# PMIC.net
KiCad netlist of a schematic drawn in Altium Designer
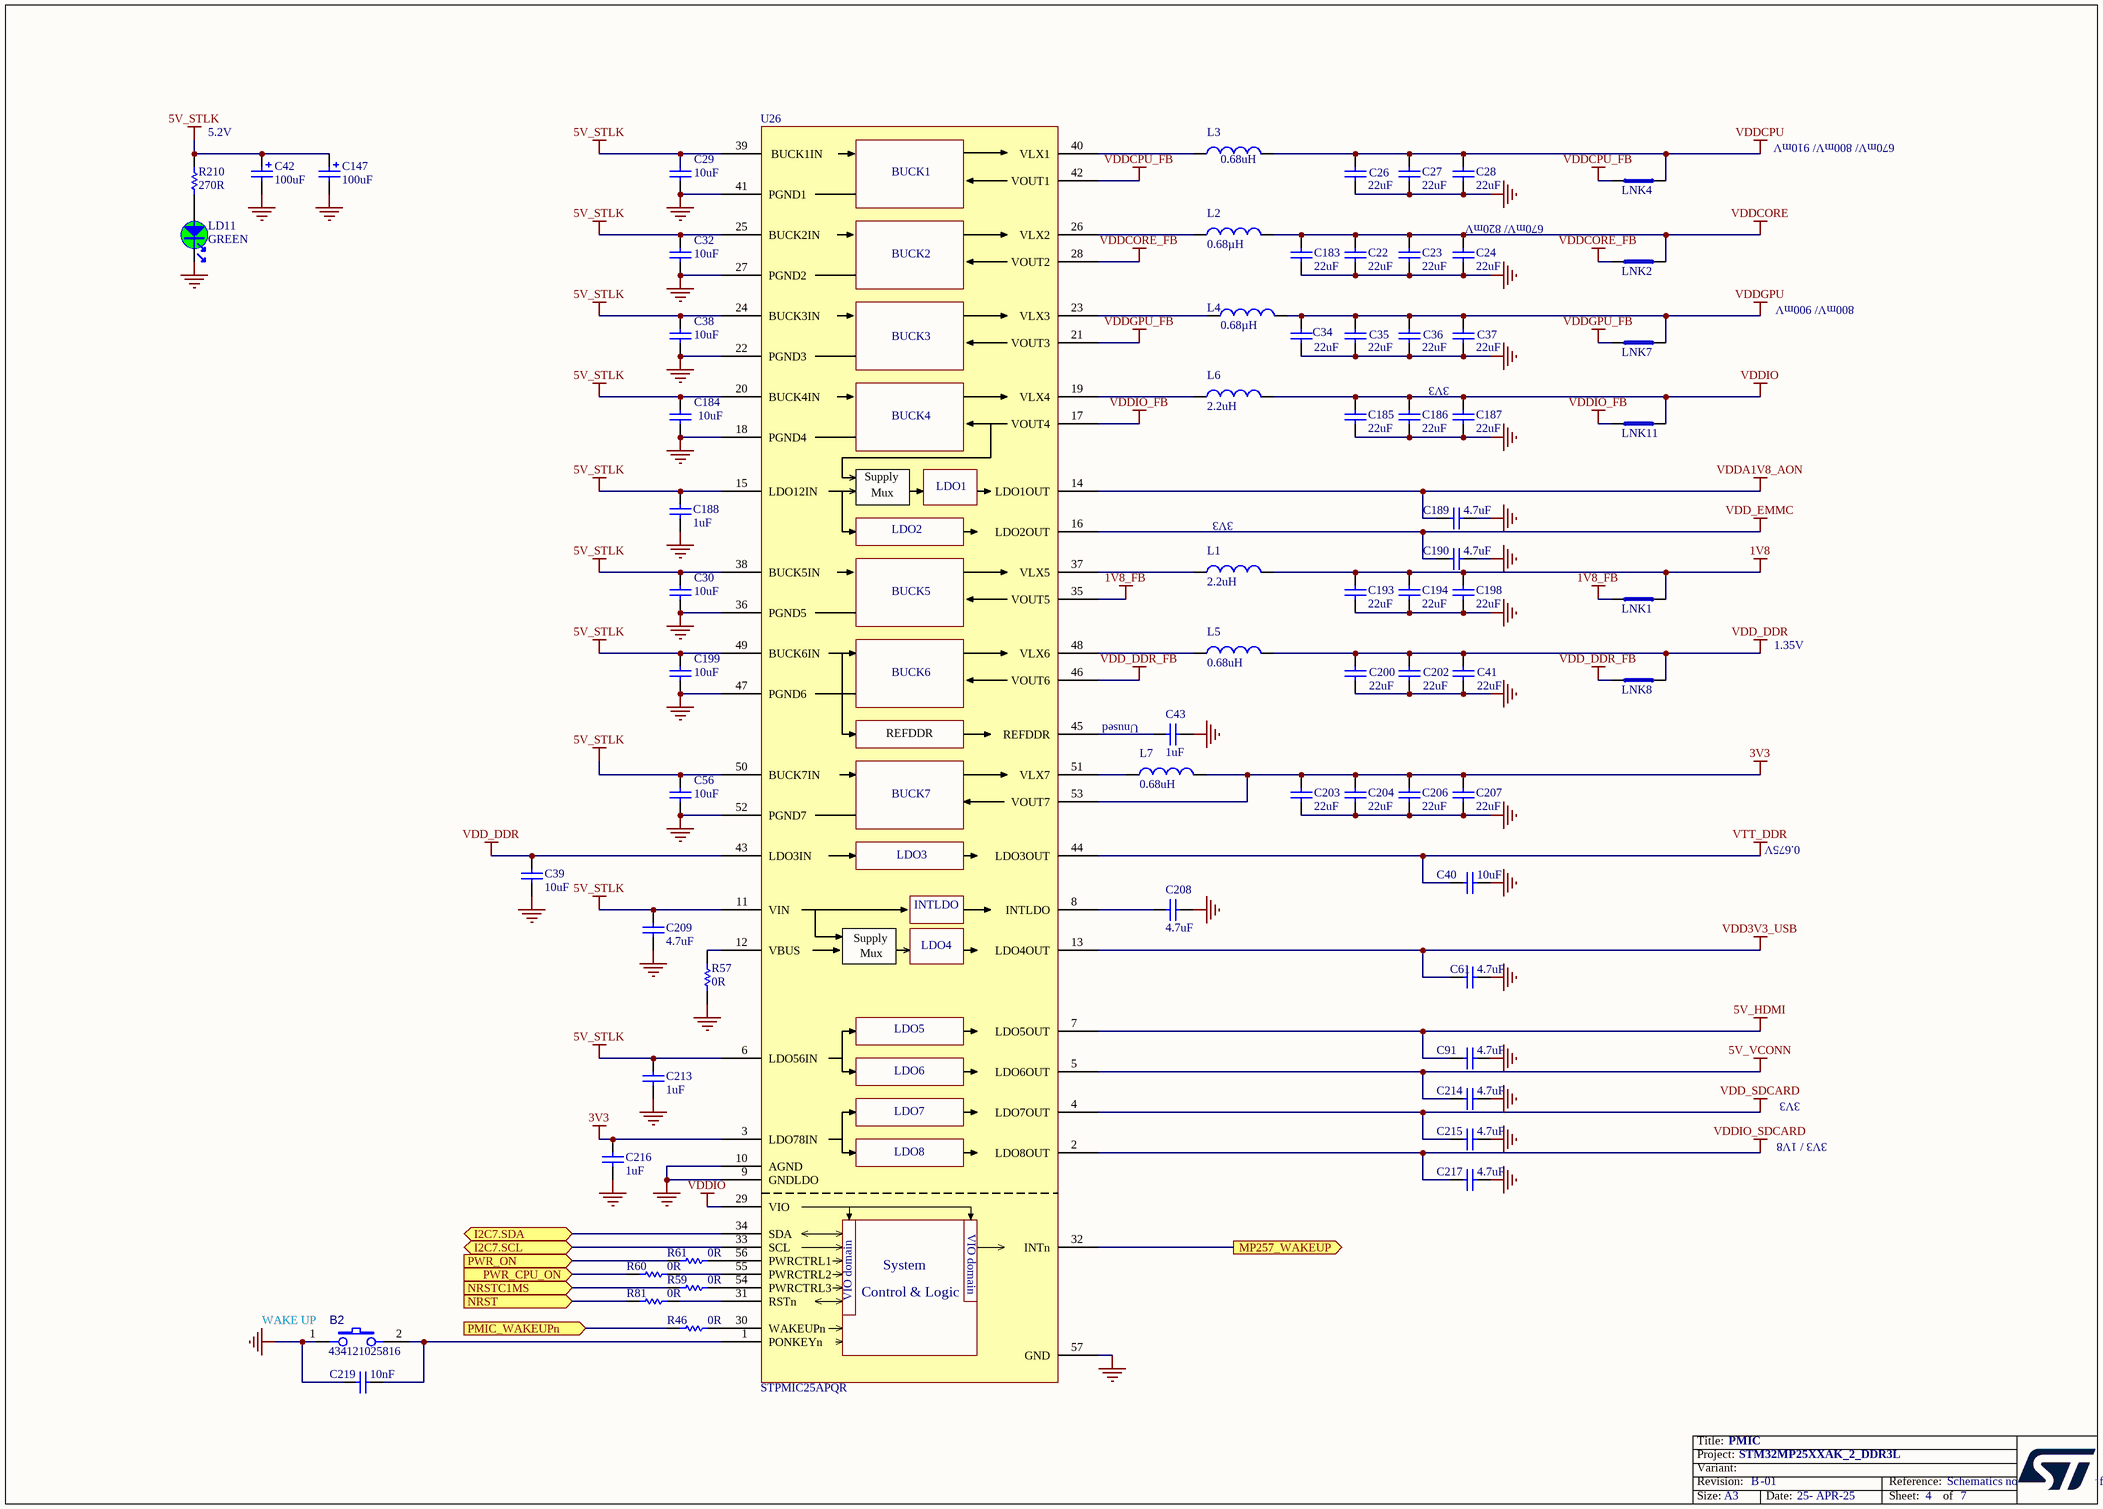
[diagram p0: PMIC.SchDoc]

(export (version "E")
  (design (tool "Eeschema 10.0.6"))
  (components
    (comp (ref "B2")
      (value "434121025816")
      (footprint "SWI_WE_434121025816")
      (description "Switch tactile, SPST-NO, 50mA, 12V, 6x3.8mm")
      (fields
        (field (name "INTERNAL_PART_NUMBER") "MCD-03492")
        (field (name "MANUFACTURER") "WURTH ELEKTRONIC")
      )
      (libsource (lib "MCD_PARTS_database") (part "SW_PUSH_SMD_2P"))
    )
    (comp (ref "C22")
      (value "22uF")
      (footprint "C0603")
      (description "Capacitor, MLCC, 22uF, 6V3, X5R, +/-20%, 0603, T=0,8mm")
      (fields
        (field (name "INTERNAL_PART_NUMBER") "MCD-00100")
        (field (name "MANUFACTURER_PART_NUMBER") "GRM188R60J226MEA0J")
      )
      (libsource (lib "MCD_PARTS_database") (part "Capacitor"))
    )
    (comp (ref "C23")
      (value "22uF")
      (footprint "C0603")
      (description "Capacitor, MLCC, 22uF, 6V3, X5R, +/-20%, 0603, T=0,8mm")
      (fields
        (field (name "INTERNAL_PART_NUMBER") "MCD-00100")
        (field (name "MANUFACTURER_PART_NUMBER") "GRM188R60J226MEA0J")
      )
      (libsource (lib "MCD_PARTS_database") (part "Capacitor"))
    )
    (comp (ref "C24")
      (value "22uF")
      (footprint "C0603")
      (description "Capacitor, MLCC, 22uF, 6V3, X5R, +/-20%, 0603, T=0,8mm")
      (fields
        (field (name "INTERNAL_PART_NUMBER") "MCD-00100")
        (field (name "MANUFACTURER_PART_NUMBER") "GRM188R60J226MEA0J")
      )
      (libsource (lib "MCD_PARTS_database") (part "Capacitor"))
    )
    (comp (ref "C26")
      (value "22uF")
      (footprint "C0603")
      (description "Capacitor, MLCC, 22uF, 6V3, X5R, +/-20%, 0603, T=0,8mm")
      (fields
        (field (name "INTERNAL_PART_NUMBER") "MCD-00100")
        (field (name "MANUFACTURER_PART_NUMBER") "GRM188R60J226MEA0J")
      )
      (libsource (lib "MCD_PARTS_database") (part "Capacitor"))
    )
    (comp (ref "C27")
      (value "22uF")
      (footprint "C0603")
      (description "Capacitor, MLCC, 22uF, 6V3, X5R, +/-20%, 0603, T=0,8mm")
      (fields (field (name "INTERNAL_PART_NUMBER") "MCD-00100") (field (name "MANUFACTURER") "MURATA"))
      (libsource (lib "MCD_PARTS_database") (part "Capacitor"))
    )
    (comp (ref "C28")
      (value "22uF")
      (footprint "C0603")
      (description "Capacitor, MLCC, 22uF, 6V3, X5R, +/-20%, 0603, T=0,8mm")
      (fields (field (name "INTERNAL_PART_NUMBER") "MCD-00100") (field (name "MANUFACTURER") "MURATA"))
      (libsource (lib "MCD_PARTS_database") (part "Capacitor"))
    )
    (comp (ref "C29")
      (value "10uF")
      (footprint "C0603")
      (description "Capacitor, MLCC, 10uF, 10V, X5R, +/-10%, 0603, T=0,8mm")
      (fields
        (field (name "INTERNAL_PART_NUMBER") "MCD-00099")
        (field (name "MANUFACTURER_PART_NUMBER") "GRM188R61A106KE69D")
      )
      (libsource (lib "MCD_PARTS_database") (part "Capacitor"))
    )
    (comp (ref "C30")
      (value "10uF")
      (footprint "C0603")
      (description "Capacitor, MLCC, 10uF, 10V, X5R, +/-10%, 0603, T=0,8mm")
      (fields
        (field (name "INTERNAL_PART_NUMBER") "MCD-00099")
        (field (name "MANUFACTURER_PART_NUMBER") "GRM188R61A106KE69D")
      )
      (libsource (lib "MCD_PARTS_database") (part "Capacitor"))
    )
    (comp (ref "C32")
      (value "10uF")
      (footprint "C0603")
      (description "Capacitor, MLCC, 10uF, 10V, X5R, +/-10%, 0603, T=0,8mm")
      (fields
        (field (name "INTERNAL_PART_NUMBER") "MCD-00099")
        (field (name "MANUFACTURER_PART_NUMBER") "GRM188R61A106KE69D")
      )
      (libsource (lib "MCD_PARTS_database") (part "Capacitor"))
    )
    (comp (ref "C34")
      (value "22uF")
      (footprint "C0603")
      (description "Capacitor, MLCC, 22uF, 6V3, X5R, +/-20%, 0603, T=0,8mm")
      (fields
        (field (name "INTERNAL_PART_NUMBER") "MCD-00100")
        (field (name "MANUFACTURER_PART_NUMBER") "GRM188R60J226MEA0J")
      )
      (libsource (lib "MCD_PARTS_database") (part "Capacitor"))
    )
    (comp (ref "C35")
      (value "22uF")
      (footprint "C0603")
      (description "Capacitor, MLCC, 22uF, 6V3, X5R, +/-20%, 0603, T=0,8mm")
      (fields
        (field (name "INTERNAL_PART_NUMBER") "MCD-00100")
        (field (name "MANUFACTURER_PART_NUMBER") "GRM188R60J226MEA0J")
      )
      (libsource (lib "MCD_PARTS_database") (part "Capacitor"))
    )
    (comp (ref "C36")
      (value "22uF")
      (footprint "C0603")
      (description "Capacitor, MLCC, 22uF, 6V3, X5R, +/-20%, 0603, T=0,8mm")
      (fields
        (field (name "INTERNAL_PART_NUMBER") "MCD-00100")
        (field (name "MANUFACTURER_PART_NUMBER") "GRM188R60J226MEA0J")
      )
      (libsource (lib "MCD_PARTS_database") (part "Capacitor"))
    )
    (comp (ref "C37")
      (value "22uF")
      (footprint "C0603")
      (description "Capacitor, MLCC, 22uF, 6V3, X5R, +/-20%, 0603, T=0,8mm")
      (fields
        (field (name "INTERNAL_PART_NUMBER") "MCD-00100")
        (field (name "MANUFACTURER_PART_NUMBER") "GRM188R60J226MEA0J")
      )
      (libsource (lib "MCD_PARTS_database") (part "Capacitor"))
    )
    (comp (ref "C38")
      (value "10uF")
      (footprint "C0603")
      (description "Capacitor, MLCC, 10uF, 10V, X5R, +/-10%, 0603, T=0,8mm")
      (fields
        (field (name "INTERNAL_PART_NUMBER") "MCD-00099")
        (field (name "MANUFACTURER_PART_NUMBER") "GRM188R61A106KE69D")
      )
      (libsource (lib "MCD_PARTS_database") (part "Capacitor"))
    )
    (comp (ref "C39")
      (value "10uF")
      (footprint "MCD_PARTS:C0402")
      (description "Capacitor, MLCC, 10uF, 6.3V, X5R, +/-20%, 0402, T=0.5mm")
      (fields (field (name "INTERNAL_PART_NUMBER") "MCD-03140") (field (name "MANUFACTURER") "MURATA"))
      (libsource (lib "MCD_PARTS_database") (part "Capacitor"))
    )
    (comp (ref "C40")
      (value "10uF")
      (footprint "C0402")
      (description "Capacitor, MLCC, 10uF, 6.3V, X5R, +/-20%, 0402, T=0.5mm")
      (fields (field (name "INTERNAL_PART_NUMBER") "MCD-03140") (field (name "MANUFACTURER") "MURATA"))
      (libsource (lib "MCD_PARTS_database") (part "Capacitor"))
    )
    (comp (ref "C41")
      (value "22uF")
      (footprint "C0603")
      (description "Capacitor, MLCC, 22uF, 6V3, X5R, +/-20%, 0603, T=0,8mm")
      (fields
        (field (name "INTERNAL_PART_NUMBER") "MCD-00100")
        (field (name "MANUFACTURER_PART_NUMBER") "GRM188R60J226MEA0J")
      )
      (libsource (lib "MCD_PARTS_database") (part "Capacitor"))
    )
    (comp (ref "C42")
      (value "100uF")
      (footprint "CPOL_TCJ-B_1210_H210")
      (description "Capacitor, Tantalum, 100uF, 6V3, 40mR, +/-20%,  Type_B (3528 metric), T=1.9mm")
      (fields (field (name "INTERNAL_PART_NUMBER") "MCD-01796") (field (name "MANUFACTURER") "AVX"))
      (libsource (lib "MCD_PARTS_database") (part "Cap_POL_TANA"))
    )
    (comp (ref "C43")
      (value "1uF")
      (footprint "C0402")
      (description "Capacitor, MLCC, 1uF, 25V, X5R, +/-10%, 0402, T=0.5mm")
      (fields (field (name "INTERNAL_PART_NUMBER") "MCD-00095") (field (name "MANUFACTURER") "MURATA"))
      (libsource (lib "MCD_PARTS_database") (part "Capacitor"))
    )
    (comp (ref "C56")
      (value "10uF")
      (footprint "C0603")
      (description "Capacitor, MLCC, 10uF, 10V, X5R, +/-10%, 0603, T=0,8mm")
      (fields
        (field (name "INTERNAL_PART_NUMBER") "MCD-00099")
        (field (name "MANUFACTURER_PART_NUMBER") "GRM188R61A106KE69D")
      )
      (libsource (lib "MCD_PARTS_database") (part "Capacitor"))
    )
    (comp (ref "C61")
      (value "4.7uF")
      (footprint "C0402")
      (description "Capacitor, MLCC, 4.7uF, 6V3, X5R, +/-20%, 0402, T=0.5mm")
      (fields
        (field (name "INTERNAL_PART_NUMBER") "MCD-01356")
        (field (name "MANUFACTURER_PART_NUMBER") "GRM155R60J475ME47")
      )
      (libsource (lib "MCD_PARTS_database") (part "Capacitor"))
    )
    (comp (ref "C91")
      (value "4.7uF")
      (footprint "C0402")
      (description "Capacitor, MLCC, 4.7uF, 6V3, X5R, +/-20%, 0402, T=0.5mm")
      (fields
        (field (name "INTERNAL_PART_NUMBER") "MCD-01356")
        (field (name "MANUFACTURER_PART_NUMBER") "GRM155R60J475ME47")
      )
      (libsource (lib "MCD_PARTS_database") (part "Capacitor"))
    )
    (comp (ref "C147")
      (value "100uF")
      (footprint "CPOL_TCJ-B_1210_H210")
      (description "Capacitor, Tantalum, 100uF, 6V3, 40mR, +/-20%,  Type_B (3528 metric), T=1.9mm")
      (fields (field (name "INTERNAL_PART_NUMBER") "MCD-01796") (field (name "MANUFACTURER") "AVX"))
      (libsource (lib "MCD_PARTS_database") (part "Cap_POL_TANA"))
    )
    (comp (ref "C183")
      (value "22uF")
      (footprint "C0603")
      (description "Capacitor, MLCC, 22uF, 6V3, X5R, +/-20%, 0603, T=0,8mm")
      (fields (field (name "INTERNAL_PART_NUMBER") "MCD-00100") (field (name "MANUFACTURER") "MURATA"))
      (libsource (lib "MCD_PARTS_database") (part "Capacitor"))
    )
    (comp (ref "C184")
      (value "10uF")
      (footprint "C0603")
      (description "Capacitor, MLCC, 10uF, 10V, X5R, +/-10%, 0603, T=0,8mm")
      (fields
        (field (name "INTERNAL_PART_NUMBER") "MCD-00099")
        (field (name "MANUFACTURER_PART_NUMBER") "GRM188R61A106KE69D")
      )
      (libsource (lib "MCD_PARTS_database") (part "Capacitor"))
    )
    (comp (ref "C185")
      (value "22uF")
      (footprint "C0805")
      (description "Capacitor, MLCC, 22uF, 10V, X5R, +/-20%, 0805, T=1,25mm")
      (fields (field (name "INTERNAL_PART_NUMBER") "MCD-03139") (field (name "MANUFACTURER") "MURATA"))
      (libsource (lib "MCD_PARTS_database") (part "Capacitor"))
    )
    (comp (ref "C186")
      (value "22uF")
      (footprint "C0805")
      (description "Capacitor, MLCC, 22uF, 10V, X5R, +/-20%, 0805, T=1,25mm")
      (fields (field (name "INTERNAL_PART_NUMBER") "MCD-03139") (field (name "MANUFACTURER") "MURATA"))
      (libsource (lib "MCD_PARTS_database") (part "Capacitor"))
    )
    (comp (ref "C187")
      (value "22uF")
      (footprint "C0805")
      (description "Capacitor, MLCC, 22uF, 10V, X5R, +/-20%, 0805, T=1,25mm")
      (fields (field (name "INTERNAL_PART_NUMBER") "MCD-03139") (field (name "MANUFACTURER") "MURATA"))
      (libsource (lib "MCD_PARTS_database") (part "Capacitor"))
    )
    (comp (ref "C188")
      (value "1uF")
      (footprint "C0402")
      (description "Capacitor, MLCC, 1uF, 25V, X5R, +/-10%, 0402, T=0.5mm")
      (fields (field (name "INTERNAL_PART_NUMBER") "MCD-00095") (field (name "MANUFACTURER") "MURATA"))
      (libsource (lib "MCD_PARTS_database") (part "Capacitor"))
    )
    (comp (ref "C189")
      (value "4.7uF")
      (footprint "C0402")
      (description "Capacitor, MLCC, 4.7uF, 6V3, X5R, +/-20%, 0402, T=0.5mm")
      (fields
        (field (name "INTERNAL_PART_NUMBER") "MCD-01356")
        (field (name "MANUFACTURER_PART_NUMBER") "GRM155R60J475ME47")
      )
      (libsource (lib "MCD_PARTS_database") (part "Capacitor"))
    )
    (comp (ref "C190")
      (value "4.7uF")
      (footprint "C0402")
      (description "Capacitor, MLCC, 4.7uF, 6V3, X5R, +/-20%, 0402, T=0.5mm")
      (fields
        (field (name "INTERNAL_PART_NUMBER") "MCD-01356")
        (field (name "MANUFACTURER_PART_NUMBER") "GRM155R60J475ME47")
      )
      (libsource (lib "MCD_PARTS_database") (part "Capacitor"))
    )
    (comp (ref "C193")
      (value "22uF")
      (footprint "C0805")
      (description "Capacitor, MLCC, 22uF, 10V, X5R, +/-20%, 0805, T=1,25mm")
      (fields (field (name "INTERNAL_PART_NUMBER") "MCD-03139") (field (name "MANUFACTURER") "MURATA"))
      (libsource (lib "MCD_PARTS_database") (part "Capacitor"))
    )
    (comp (ref "C194")
      (value "22uF")
      (footprint "C0805")
      (description "Capacitor, MLCC, 22uF, 10V, X5R, +/-20%, 0805, T=1,25mm")
      (fields (field (name "INTERNAL_PART_NUMBER") "MCD-03139") (field (name "MANUFACTURER") "MURATA"))
      (libsource (lib "MCD_PARTS_database") (part "Capacitor"))
    )
    (comp (ref "C198")
      (value "22uF")
      (footprint "C0805")
      (description "Capacitor, MLCC, 22uF, 10V, X5R, +/-20%, 0805, T=1,25mm")
      (fields (field (name "INTERNAL_PART_NUMBER") "MCD-03139") (field (name "MANUFACTURER") "MURATA"))
      (libsource (lib "MCD_PARTS_database") (part "Capacitor"))
    )
    (comp (ref "C199")
      (value "10uF")
      (footprint "C0603")
      (description "Capacitor, MLCC, 10uF, 10V, X5R, +/-10%, 0603, T=0,8mm")
      (fields
        (field (name "INTERNAL_PART_NUMBER") "MCD-00099")
        (field (name "MANUFACTURER_PART_NUMBER") "GRM188R61A106KE69D")
      )
      (libsource (lib "MCD_PARTS_database") (part "Capacitor"))
    )
    (comp (ref "C200")
      (value "22uF")
      (footprint "C0603")
      (description "Capacitor, MLCC, 22uF, 6V3, X5R, +/-20%, 0603, T=0,8mm")
      (fields
        (field (name "INTERNAL_PART_NUMBER") "MCD-00100")
        (field (name "MANUFACTURER_PART_NUMBER") "GRM188R60J226MEA0J")
      )
      (libsource (lib "MCD_PARTS_database") (part "Capacitor"))
    )
    (comp (ref "C202")
      (value "22uF")
      (footprint "C0603")
      (description "Capacitor, MLCC, 22uF, 6V3, X5R, +/-20%, 0603, T=0,8mm")
      (fields
        (field (name "INTERNAL_PART_NUMBER") "MCD-00100")
        (field (name "MANUFACTURER_PART_NUMBER") "GRM188R60J226MEA0J")
      )
      (libsource (lib "MCD_PARTS_database") (part "Capacitor"))
    )
    (comp (ref "C203")
      (value "22uF")
      (footprint "C0805")
      (description "Capacitor, MLCC, 22uF, 10V, X5R, +/-20%, 0805, T=1,25mm")
      (fields (field (name "INTERNAL_PART_NUMBER") "MCD-03139") (field (name "MANUFACTURER") "MURATA"))
      (libsource (lib "MCD_PARTS_database") (part "Capacitor"))
    )
    (comp (ref "C204")
      (value "22uF")
      (footprint "C0805")
      (description "Capacitor, MLCC, 22uF, 10V, X5R, +/-20%, 0805, T=1,25mm")
      (fields (field (name "INTERNAL_PART_NUMBER") "MCD-03139") (field (name "MANUFACTURER") "MURATA"))
      (libsource (lib "MCD_PARTS_database") (part "Capacitor"))
    )
    (comp (ref "C206")
      (value "22uF")
      (footprint "C0805")
      (description "Capacitor, MLCC, 22uF, 10V, X5R, +/-20%, 0805, T=1,25mm")
      (fields (field (name "INTERNAL_PART_NUMBER") "MCD-03139") (field (name "MANUFACTURER") "MURATA"))
      (libsource (lib "MCD_PARTS_database") (part "Capacitor"))
    )
    (comp (ref "C207")
      (value "22uF")
      (footprint "C0805")
      (description "Capacitor, MLCC, 22uF, 10V, X5R, +/-20%, 0805, T=1,25mm")
      (fields (field (name "INTERNAL_PART_NUMBER") "MCD-03139") (field (name "MANUFACTURER") "MURATA"))
      (libsource (lib "MCD_PARTS_database") (part "Capacitor"))
    )
    (comp (ref "C208")
      (value "4.7uF")
      (footprint "C0402")
      (description "Capacitor, MLCC, 4.7uF, 6V3, X5R, +/-20%, 0402, T=0.5mm")
      (fields
        (field (name "INTERNAL_PART_NUMBER") "MCD-01356")
        (field (name "MANUFACTURER_PART_NUMBER") "GRM155R60J475ME47")
      )
      (libsource (lib "MCD_PARTS_database") (part "Capacitor"))
    )
    (comp (ref "C209")
      (value "4.7uF")
      (footprint "C0402")
      (description "Capacitor, MLCC, 4.7uF, 6V3, X5R, +/-20%, 0402, T=0.5mm")
      (fields
        (field (name "INTERNAL_PART_NUMBER") "MCD-01356")
        (field (name "MANUFACTURER_PART_NUMBER") "GRM155R60J475ME47")
      )
      (libsource (lib "MCD_PARTS_database") (part "Capacitor"))
    )
    (comp (ref "C213")
      (value "1uF")
      (footprint "C0402")
      (description "Capacitor, MLCC, 1uF, 25V, X5R, +/-10%, 0402, T=0.5mm")
      (fields (field (name "INTERNAL_PART_NUMBER") "MCD-00095") (field (name "MANUFACTURER") "MURATA"))
      (libsource (lib "MCD_PARTS_database") (part "Capacitor"))
    )
    (comp (ref "C214")
      (value "4.7uF")
      (footprint "C0402")
      (description "Capacitor, MLCC, 4.7uF, 6V3, X5R, +/-20%, 0402, T=0.5mm")
      (fields
        (field (name "INTERNAL_PART_NUMBER") "MCD-01356")
        (field (name "MANUFACTURER_PART_NUMBER") "GRM155R60J475ME47")
      )
      (libsource (lib "MCD_PARTS_database") (part "Capacitor"))
    )
    (comp (ref "C215")
      (value "4.7uF")
      (footprint "C0402")
      (description "Capacitor, MLCC, 4.7uF, 6V3, X5R, +/-20%, 0402, T=0.5mm")
      (fields
        (field (name "INTERNAL_PART_NUMBER") "MCD-01356")
        (field (name "MANUFACTURER_PART_NUMBER") "GRM155R60J475ME47")
      )
      (libsource (lib "MCD_PARTS_database") (part "Capacitor"))
    )
    (comp (ref "C216")
      (value "1uF")
      (footprint "C0402")
      (description "Capacitor, MLCC, 1uF, 25V, X5R, +/-10%, 0402, T=0.5mm")
      (fields (field (name "INTERNAL_PART_NUMBER") "MCD-00095") (field (name "MANUFACTURER") "MURATA"))
      (libsource (lib "MCD_PARTS_database") (part "Capacitor"))
    )
    (comp (ref "C217")
      (value "4.7uF")
      (footprint "C0402")
      (description "Capacitor, MLCC, 4.7uF, 6V3, X5R, +/-20%, 0402, T=0.5mm")
      (fields
        (field (name "INTERNAL_PART_NUMBER") "MCD-01356")
        (field (name "MANUFACTURER_PART_NUMBER") "GRM155R60J475ME47")
      )
      (libsource (lib "MCD_PARTS_database") (part "Capacitor"))
    )
    (comp (ref "C219")
      (value "10nF")
      (footprint "C0402")
      (description "Capacitor, MLCC, 10nF, 50V, X7R, +/-10%, 0402, T=0.5mm")
      (fields
        (field (name "INTERNAL_PART_NUMBER") "MCD-02198")
        (field (name "MANUFACTURER_PART_NUMBER") "CC0402KRX7R9BB103")
      )
      (libsource (lib "MCD_PARTS_database") (part "Capacitor"))
    )
    (comp (ref "L1")
      (value "2.2uH")
      (footprint "IND_2016_MURATA_LQM2MPN2R2NG0")
      (description "Inductor, 2.2uH, +/-20%, Itemp= 1700mA, Isat= 2400mA, 0R140, 0806, T=1mm")
      (fields (field (name "INTERNAL_PART_NUMBER") "MCD-03143") (field (name "MANUFACTURER") "MURATA"))
      (libsource (lib "MCD_PARTS_database") (part "Inductor"))
    )
    (comp (ref "L2")
      (value "0.68µH")
      (footprint "IND_2520_TOKO_DFE252012P")
      (description "Inductor, 0.68uH, +/-20%, Itemp= 3900mA, Isat= 5400mA, 0R031, 1008, T=1.2mm")
      (fields (field (name "INTERNAL_PART_NUMBER") "MCD-03142") (field (name "MANUFACTURER") "MURATA"))
      (libsource (lib "MCD_PARTS_database") (part "Inductor"))
    )
    (comp (ref "L3")
      (value "0.68uH")
      (footprint "IND_2016_MURATA_LQM2MPN2R2NG0")
      (description "Inductor, 0.68uH, +/-20%, Itemp= 3100mA, Isat= 4300mA, 0R043, 0806, T=1mm")
      (fields (field (name "INTERNAL_PART_NUMBER") "MCD-03141") (field (name "MANUFACTURER") "MURATA"))
      (libsource (lib "MCD_PARTS_database") (part "Inductor"))
    )
    (comp (ref "L4")
      (value "0.68µH")
      (footprint "IND_2520_TOKO_DFE252012P")
      (description "Inductor, 0.68uH, +/-20%, Itemp= 3900mA, Isat= 5400mA, 0R031, 1008, T=1.2mm")
      (fields (field (name "INTERNAL_PART_NUMBER") "MCD-03142") (field (name "MANUFACTURER") "MURATA"))
      (libsource (lib "MCD_PARTS_database") (part "Inductor"))
    )
    (comp (ref "L5")
      (value "0.68uH")
      (footprint "IND_2016_MURATA_LQM2MPN2R2NG0")
      (description "Inductor, 0.68uH, +/-20%, Itemp= 3100mA, Isat= 4300mA, 0R043, 0806, T=1mm")
      (fields (field (name "INTERNAL_PART_NUMBER") "MCD-03141") (field (name "MANUFACTURER") "MURATA"))
      (libsource (lib "MCD_PARTS_database") (part "Inductor"))
    )
    (comp (ref "L6")
      (value "2.2uH")
      (footprint "IND_2016_MURATA_LQM2MPN2R2NG0")
      (description "Inductor, 2.2uH, +/-20%, Itemp= 1700mA, Isat= 2400mA, 0R140, 0806, T=1mm")
      (fields (field (name "INTERNAL_PART_NUMBER") "MCD-03143") (field (name "MANUFACTURER") "MURATA"))
      (libsource (lib "MCD_PARTS_database") (part "Inductor"))
    )
    (comp (ref "L7")
      (value "0.68uH")
      (footprint "IND_2016_MURATA_LQM2MPN2R2NG0")
      (description "Inductor, 0.68uH, +/-20%, Itemp= 3100mA, Isat= 4300mA, 0R043, 0806, T=1mm")
      (fields (field (name "INTERNAL_PART_NUMBER") "MCD-03141") (field (name "MANUFACTURER") "MURATA"))
      (libsource (lib "MCD_PARTS_database") (part "Inductor"))
    )
    (comp (ref "LD11")
      (value "GREEN")
      (footprint "LED_0603_OSRAM_LG-Q396-PS-35_GREEN_1A2K_H0P4")
      (description "LED Green, 0603 SMD, Forward Voltage Typ=2V, Max=2.5V")
      (fields
        (field (name "INTERNAL_PART_NUMBER") "MCD-00588")
        (field (name "MANUFACTURER_PART_NUMBER") "LG Q396-PS-35")
        (field (name "PROVIDED_BY") "SUBCO")
      )
      (libsource (lib "MCD_PARTS_database") (part "LED_green"))
    )
    (comp (ref "LNK1")
      (value "link_200")
      (footprint "LINK200")
      (description "Track link on PCB 200um width for layout routing")
      (fields (field (name "INTERNAL_PART_NUMBER") "MCD-02777"))
      (libsource (lib "MCD_PARTS_database") (part "link_200"))
    )
    (comp (ref "LNK2")
      (value "link_200")
      (footprint "LINK200")
      (description "Track link on PCB 200um width for layout routing")
      (fields (field (name "INTERNAL_PART_NUMBER") "MCD-02777"))
      (libsource (lib "MCD_PARTS_database") (part "link_200"))
    )
    (comp (ref "LNK4")
      (value "link_200")
      (footprint "LINK200")
      (description "Track link on PCB 200um width for layout routing")
      (fields (field (name "INTERNAL_PART_NUMBER") "MCD-02777"))
      (libsource (lib "MCD_PARTS_database") (part "link_200"))
    )
    (comp (ref "LNK7")
      (value "link_200")
      (footprint "LINK200")
      (description "Track link on PCB 200um width for layout routing")
      (fields (field (name "INTERNAL_PART_NUMBER") "MCD-02777"))
      (libsource (lib "MCD_PARTS_database") (part "link_200"))
    )
    (comp (ref "LNK8")
      (value "link_200")
      (footprint "LINK200")
      (description "Track link on PCB 200um width for layout routing")
      (fields (field (name "INTERNAL_PART_NUMBER") "MCD-02777"))
      (libsource (lib "MCD_PARTS_database") (part "link_200"))
    )
    (comp (ref "LNK11")
      (value "link_200")
      (footprint "LINK200")
      (description "Track link on PCB 200um width for layout routing")
      (fields (field (name "INTERNAL_PART_NUMBER") "MCD-02777"))
      (libsource (lib "MCD_PARTS_database") (part "link_200"))
    )
    (comp (ref "R46")
      (value "0R")
      (footprint "R0402")
      (description "Resistor,0R,0402,5%,1/16W")
      (fields
        (field (name "INTERNAL_PART_NUMBER") "MCD-00052")
        (field (name "MANUFACTURER_PART_NUMBER") "RC0402JR-070RL")
        (field (name "PROVIDED_BY") "SUBCO")
      )
      (libsource (lib "MCD_PARTS_database") (part "Resistor"))
    )
    (comp (ref "R57")
      (value "0R")
      (footprint "R0402")
      (description "Resistor,0R,0402,5%,1/16W")
      (fields
        (field (name "INTERNAL_PART_NUMBER") "MCD-00052")
        (field (name "MANUFACTURER_PART_NUMBER") "RC0402JR-070RL")
        (field (name "PROVIDED_BY") "SUBCO")
      )
      (libsource (lib "MCD_PARTS_database") (part "Resistor"))
    )
    (comp (ref "R59")
      (value "0R")
      (footprint "R0402")
      (description "Resistor,0R,0402,5%,1/16W")
      (fields
        (field (name "INTERNAL_PART_NUMBER") "MCD-00052")
        (field (name "MANUFACTURER_PART_NUMBER") "RC0402JR-070RL")
        (field (name "PROVIDED_BY") "SUBCO")
      )
      (libsource (lib "MCD_PARTS_database") (part "Resistor"))
    )
    (comp (ref "R60")
      (value "0R")
      (footprint "R0402")
      (description "Resistor,0R,0402,5%,1/16W")
      (fields
        (field (name "INTERNAL_PART_NUMBER") "MCD-00052")
        (field (name "MANUFACTURER_PART_NUMBER") "RC0402JR-070RL")
        (field (name "PROVIDED_BY") "SUBCO")
      )
      (libsource (lib "MCD_PARTS_database") (part "Resistor"))
    )
    (comp (ref "R61")
      (value "0R")
      (footprint "R0402")
      (description "Resistor,0R,0402,5%,1/16W")
      (fields
        (field (name "INTERNAL_PART_NUMBER") "MCD-00052")
        (field (name "MANUFACTURER_PART_NUMBER") "RC0402JR-070RL")
        (field (name "PROVIDED_BY") "SUBCO")
      )
      (libsource (lib "MCD_PARTS_database") (part "Resistor"))
    )
    (comp (ref "R81")
      (value "0R")
      (footprint "R0402")
      (description "Resistor,0R,0402,5%,1/16W")
      (fields
        (field (name "INTERNAL_PART_NUMBER") "MCD-00052")
        (field (name "MANUFACTURER_PART_NUMBER") "RC0402JR-070RL")
        (field (name "PROVIDED_BY") "SUBCO")
      )
      (libsource (lib "MCD_PARTS_database") (part "Resistor"))
    )
    (comp (ref "R210")
      (value "270R")
      (footprint "R0402")
      (description "Resistor,270R,0402,1%,1/16W")
      (fields
        (field (name "INTERNAL_PART_NUMBER") "MCD-00441")
        (field (name "MANUFACTURER_PART_NUMBER") "RC0402FR-07270RL")
        (field (name "PROVIDED_BY") "SUBCO")
      )
      (libsource (lib "MCD_PARTS_database") (part "Resistor"))
    )
    (comp (ref "U26")
      (value "STPMIC25APQR")
      (footprint "ICC_QFN56-EPAD_6P5X6P5_P040")
      (description "STPMIC2")
      (fields
        (field (name "INTERNAL_PART_NUMBER") "MCD-03000")
        (field (name "MANUFACTURER") "STMICROELECTRONICS")
      )
      (libsource (lib "MCD_PARTS_database") (part "STPMIC2"))
    )
  )
  (nets
    (net (code "1") (name "/I2C7.SCL") (class "Default")
      (node (ref "U26") (pin "33") (pinfunction "SCL_33") (pintype "passive"))
    )
    (net (code "2") (name "/I2C7.SDA") (class "Default")
      (node (ref "U26") (pin "34") (pinfunction "SDA_34") (pintype "passive"))
    )
    (net (code "3") (name "/MP257_WAKEUP") (class "Default")
      (node (ref "U26") (pin "32") (pinfunction "INTn_32") (pintype "passive"))
    )
    (net (code "4") (name "/NRST") (class "Default")
      (node (ref "R81") (pin "1") (pinfunction "1_1") (pintype "passive"))
    )
    (net (code "5") (name "/NRSTC1MS") (class "Default")
      (node (ref "R59") (pin "1") (pinfunction "1_1") (pintype "passive"))
    )
    (net (code "6") (name "/PMIC_WAKEUPn") (class "Default")
      (node (ref "R46") (pin "1") (pinfunction "1_1") (pintype "passive"))
    )
    (net (code "7") (name "/PWR_CPU_ON") (class "Default")
      (node (ref "R60") (pin "1") (pinfunction "1_1") (pintype "passive"))
    )
    (net (code "8") (name "/PWR_ON") (class "Default")
      (node (ref "R61") (pin "1") (pinfunction "1_1") (pintype "passive"))
    )
    (net (code "9") (name "1V8") (class "Default")
      (node (ref "C193") (pin "2") (pinfunction "2_2") (pintype "passive"))
      (node (ref "C194") (pin "2") (pinfunction "2_2") (pintype "passive"))
      (node (ref "C198") (pin "2") (pinfunction "2_2") (pintype "passive"))
      (node (ref "L1") (pin "2") (pinfunction "2_2") (pintype "passive"))
      (node (ref "LNK1") (pin "2") (pinfunction "2_2") (pintype "passive"))
    )
    (net (code "10") (name "1V8_FB") (class "Default")
      (node (ref "LNK1") (pin "1") (pinfunction "1_1") (pintype "passive"))
      (node (ref "U26") (pin "35") (pinfunction "VOUT5_35") (pintype "passive"))
    )
    (net (code "11") (name "3V3") (class "Default")
      (node (ref "C203") (pin "2") (pinfunction "2_2") (pintype "passive"))
      (node (ref "C204") (pin "2") (pinfunction "2_2") (pintype "passive"))
      (node (ref "C206") (pin "2") (pinfunction "2_2") (pintype "passive"))
      (node (ref "C207") (pin "2") (pinfunction "2_2") (pintype "passive"))
      (node (ref "C216") (pin "2") (pinfunction "2_2") (pintype "passive"))
      (node (ref "L7") (pin "2") (pinfunction "2_2") (pintype "passive"))
      (node (ref "U26") (pin "3") (pinfunction "LDO78IN_3") (pintype "passive"))
      (node (ref "U26") (pin "53") (pinfunction "VOUT7_53") (pintype "passive"))
    )
    (net (code "12") (name "5V_HDMI") (class "Default")
      (node (ref "C91") (pin "1") (pinfunction "1_1") (pintype "passive"))
      (node (ref "U26") (pin "7") (pinfunction "LDO5OUT_7") (pintype "passive"))
    )
    (net (code "13") (name "5V_STLK") (class "Default")
      (node (ref "C147") (pin "1") (pinfunction "1_1") (pintype "passive"))
      (node (ref "C184") (pin "2") (pinfunction "2_2") (pintype "passive"))
      (node (ref "C188") (pin "2") (pinfunction "2_2") (pintype "passive"))
      (node (ref "C199") (pin "2") (pinfunction "2_2") (pintype "passive"))
      (node (ref "C209") (pin "2") (pinfunction "2_2") (pintype "passive"))
      (node (ref "C213") (pin "2") (pinfunction "2_2") (pintype "passive"))
      (node (ref "C29") (pin "2") (pinfunction "2_2") (pintype "passive"))
      (node (ref "C30") (pin "2") (pinfunction "2_2") (pintype "passive"))
      (node (ref "C32") (pin "2") (pinfunction "2_2") (pintype "passive"))
      (node (ref "C38") (pin "2") (pinfunction "2_2") (pintype "passive"))
      (node (ref "C42") (pin "1") (pinfunction "1_1") (pintype "passive"))
      (node (ref "C56") (pin "2") (pinfunction "2_2") (pintype "passive"))
      (node (ref "R210") (pin "1") (pinfunction "1_1") (pintype "passive"))
      (node (ref "U26") (pin "11") (pinfunction "VIN_11") (pintype "passive"))
      (node (ref "U26") (pin "15") (pinfunction "LDO12IN_15") (pintype "passive"))
      (node (ref "U26") (pin "20") (pinfunction "BUCK4IN_20") (pintype "passive"))
      (node (ref "U26") (pin "24") (pinfunction "BUCK3IN_24") (pintype "passive"))
      (node (ref "U26") (pin "25") (pinfunction "BUCK2IN_25") (pintype "passive"))
      (node (ref "U26") (pin "38") (pinfunction "BUCK5IN_38") (pintype "passive"))
      (node (ref "U26") (pin "39") (pinfunction "BUCK1IN_39") (pintype "passive"))
      (node (ref "U26") (pin "49") (pinfunction "BUCK6IN_49") (pintype "passive"))
      (node (ref "U26") (pin "50") (pinfunction "BUCK7IN_50") (pintype "passive"))
      (node (ref "U26") (pin "6") (pinfunction "LDO56IN_6") (pintype "passive"))
    )
    (net (code "14") (name "5V_VCONN") (class "Default")
      (node (ref "C214") (pin "1") (pinfunction "1_1") (pintype "passive"))
      (node (ref "U26") (pin "5") (pinfunction "LDO6OUT_5") (pintype "passive"))
    )
    (net (code "15") (name "GND") (class "Default")
      (node (ref "B2") (pin "1") (pinfunction "1_1") (pintype "passive"))
      (node (ref "C147") (pin "2") (pinfunction "2_2") (pintype "passive"))
      (node (ref "C183") (pin "1") (pinfunction "1_1") (pintype "passive"))
      (node (ref "C184") (pin "1") (pinfunction "1_1") (pintype "passive"))
      (node (ref "C185") (pin "1") (pinfunction "1_1") (pintype "passive"))
      (node (ref "C186") (pin "1") (pinfunction "1_1") (pintype "passive"))
      (node (ref "C187") (pin "1") (pinfunction "1_1") (pintype "passive"))
      (node (ref "C188") (pin "1") (pinfunction "1_1") (pintype "passive"))
      (node (ref "C189") (pin "1") (pinfunction "1_1") (pintype "passive"))
      (node (ref "C190") (pin "2") (pinfunction "2_2") (pintype "passive"))
      (node (ref "C193") (pin "1") (pinfunction "1_1") (pintype "passive"))
      (node (ref "C194") (pin "1") (pinfunction "1_1") (pintype "passive"))
      (node (ref "C198") (pin "1") (pinfunction "1_1") (pintype "passive"))
      (node (ref "C199") (pin "1") (pinfunction "1_1") (pintype "passive"))
      (node (ref "C200") (pin "1") (pinfunction "1_1") (pintype "passive"))
      (node (ref "C202") (pin "1") (pinfunction "1_1") (pintype "passive"))
      (node (ref "C203") (pin "1") (pinfunction "1_1") (pintype "passive"))
      (node (ref "C204") (pin "1") (pinfunction "1_1") (pintype "passive"))
      (node (ref "C206") (pin "1") (pinfunction "1_1") (pintype "passive"))
      (node (ref "C207") (pin "1") (pinfunction "1_1") (pintype "passive"))
      (node (ref "C208") (pin "2") (pinfunction "2_2") (pintype "passive"))
      (node (ref "C209") (pin "1") (pinfunction "1_1") (pintype "passive"))
      (node (ref "C213") (pin "1") (pinfunction "1_1") (pintype "passive"))
      (node (ref "C214") (pin "2") (pinfunction "2_2") (pintype "passive"))
      (node (ref "C215") (pin "2") (pinfunction "2_2") (pintype "passive"))
      (node (ref "C216") (pin "1") (pinfunction "1_1") (pintype "passive"))
      (node (ref "C217") (pin "2") (pinfunction "2_2") (pintype "passive"))
      (node (ref "C219") (pin "1") (pinfunction "1_1") (pintype "passive"))
      (node (ref "C22") (pin "1") (pinfunction "1_1") (pintype "passive"))
      (node (ref "C23") (pin "1") (pinfunction "1_1") (pintype "passive"))
      (node (ref "C24") (pin "1") (pinfunction "1_1") (pintype "passive"))
      (node (ref "C26") (pin "1") (pinfunction "1_1") (pintype "passive"))
      (node (ref "C27") (pin "1") (pinfunction "1_1") (pintype "passive"))
      (node (ref "C28") (pin "1") (pinfunction "1_1") (pintype "passive"))
      (node (ref "C29") (pin "1") (pinfunction "1_1") (pintype "passive"))
      (node (ref "C30") (pin "1") (pinfunction "1_1") (pintype "passive"))
      (node (ref "C32") (pin "1") (pinfunction "1_1") (pintype "passive"))
      (node (ref "C34") (pin "1") (pinfunction "1_1") (pintype "passive"))
      (node (ref "C35") (pin "1") (pinfunction "1_1") (pintype "passive"))
      (node (ref "C36") (pin "1") (pinfunction "1_1") (pintype "passive"))
      (node (ref "C37") (pin "1") (pinfunction "1_1") (pintype "passive"))
      (node (ref "C38") (pin "1") (pinfunction "1_1") (pintype "passive"))
      (node (ref "C39") (pin "1") (pinfunction "1_1") (pintype "passive"))
      (node (ref "C40") (pin "1") (pinfunction "1_1") (pintype "passive"))
      (node (ref "C41") (pin "1") (pinfunction "1_1") (pintype "passive"))
      (node (ref "C42") (pin "2") (pinfunction "2_2") (pintype "passive"))
      (node (ref "C43") (pin "1") (pinfunction "1_1") (pintype "passive"))
      (node (ref "C56") (pin "1") (pinfunction "1_1") (pintype "passive"))
      (node (ref "C61") (pin "1") (pinfunction "1_1") (pintype "passive"))
      (node (ref "C91") (pin "2") (pinfunction "2_2") (pintype "passive"))
      (node (ref "LD11") (pin "2") (pintype "passive"))
      (node (ref "R57") (pin "1") (pinfunction "1_1") (pintype "passive"))
      (node (ref "U26") (pin "10") (pinfunction "AGND_10") (pintype "passive"))
      (node (ref "U26") (pin "18") (pinfunction "PGND4_18") (pintype "passive"))
      (node (ref "U26") (pin "22") (pinfunction "PGND3_22") (pintype "passive"))
      (node (ref "U26") (pin "27") (pinfunction "PGND2_27") (pintype "passive"))
      (node (ref "U26") (pin "36") (pinfunction "PGND5_36") (pintype "passive"))
      (node (ref "U26") (pin "41") (pinfunction "PGND1_41") (pintype "passive"))
      (node (ref "U26") (pin "47") (pinfunction "PGND6_47") (pintype "passive"))
      (node (ref "U26") (pin "52") (pinfunction "PGND7_52") (pintype "passive"))
      (node (ref "U26") (pin "57") (pinfunction "GND_57") (pintype "passive"))
      (node (ref "U26") (pin "9") (pinfunction "GNDLDO_9") (pintype "passive"))
    )
    (net (code "16") (name "Net-(LD11-Pad1)") (class "Default")
      (node (ref "LD11") (pin "1") (pintype "passive"))
      (node (ref "R210") (pin "2") (pinfunction "2_2") (pintype "passive"))
    )
    (net (code "17") (name "Net-(U26-INTLDO)") (class "Default")
      (node (ref "C208") (pin "1") (pinfunction "1_1") (pintype "passive"))
      (node (ref "U26") (pin "8") (pinfunction "INTLDO_8") (pintype "passive"))
    )
    (net (code "18") (name "Net-(U26-PONKEYn)") (class "Default")
      (node (ref "B2") (pin "2") (pinfunction "2_2") (pintype "passive"))
      (node (ref "C219") (pin "2") (pinfunction "2_2") (pintype "passive"))
      (node (ref "U26") (pin "1") (pinfunction "PONKEYn_1") (pintype "passive"))
    )
    (net (code "19") (name "Net-(U26-PWRCTRL1)") (class "Default")
      (node (ref "R61") (pin "2") (pinfunction "2_2") (pintype "passive"))
      (node (ref "U26") (pin "56") (pinfunction "PWRCTRL1_56") (pintype "passive"))
    )
    (net (code "20") (name "Net-(U26-PWRCTRL2)") (class "Default")
      (node (ref "R60") (pin "2") (pinfunction "2_2") (pintype "passive"))
      (node (ref "U26") (pin "55") (pinfunction "PWRCTRL2_55") (pintype "passive"))
    )
    (net (code "21") (name "Net-(U26-PWRCTRL3)") (class "Default")
      (node (ref "R59") (pin "2") (pinfunction "2_2") (pintype "passive"))
      (node (ref "U26") (pin "54") (pinfunction "PWRCTRL3_54") (pintype "passive"))
    )
    (net (code "22") (name "Net-(U26-REFDDR)") (class "Default")
      (node (ref "C43") (pin "2") (pinfunction "2_2") (pintype "passive"))
      (node (ref "U26") (pin "45") (pinfunction "REFDDR_45") (pintype "passive"))
    )
    (net (code "23") (name "Net-(U26-RSTn)") (class "Default")
      (node (ref "R81") (pin "2") (pinfunction "2_2") (pintype "passive"))
      (node (ref "U26") (pin "31") (pinfunction "RSTn_31") (pintype "passive"))
    )
    (net (code "24") (name "Net-(U26-VBUS)") (class "Default")
      (node (ref "R57") (pin "2") (pinfunction "2_2") (pintype "passive"))
      (node (ref "U26") (pin "12") (pinfunction "VBUS_12") (pintype "passive"))
    )
    (net (code "25") (name "Net-(U26-VLX1)") (class "Default")
      (node (ref "L3") (pin "1") (pinfunction "1_1") (pintype "passive"))
      (node (ref "U26") (pin "40") (pinfunction "VLX1_40") (pintype "passive"))
    )
    (net (code "26") (name "Net-(U26-VLX2)") (class "Default")
      (node (ref "L2") (pin "1") (pinfunction "1_1") (pintype "passive"))
      (node (ref "U26") (pin "26") (pinfunction "VLX2_26") (pintype "passive"))
    )
    (net (code "27") (name "Net-(U26-VLX3)") (class "Default")
      (node (ref "L4") (pin "1") (pinfunction "1_1") (pintype "passive"))
      (node (ref "U26") (pin "23") (pinfunction "VLX3_23") (pintype "passive"))
    )
    (net (code "28") (name "Net-(U26-VLX4)") (class "Default")
      (node (ref "L6") (pin "1") (pinfunction "1_1") (pintype "passive"))
      (node (ref "U26") (pin "19") (pinfunction "VLX4_19") (pintype "passive"))
    )
    (net (code "29") (name "Net-(U26-VLX5)") (class "Default")
      (node (ref "L1") (pin "1") (pinfunction "1_1") (pintype "passive"))
      (node (ref "U26") (pin "37") (pinfunction "VLX5_37") (pintype "passive"))
    )
    (net (code "30") (name "Net-(U26-VLX6)") (class "Default")
      (node (ref "L5") (pin "1") (pinfunction "1_1") (pintype "passive"))
      (node (ref "U26") (pin "48") (pinfunction "VLX6_48") (pintype "passive"))
    )
    (net (code "31") (name "Net-(U26-VLX7)") (class "Default")
      (node (ref "L7") (pin "1") (pinfunction "1_1") (pintype "passive"))
      (node (ref "U26") (pin "51") (pinfunction "VLX7_51") (pintype "passive"))
    )
    (net (code "32") (name "Net-(U26-WAKEUPn)") (class "Default")
      (node (ref "R46") (pin "2") (pinfunction "2_2") (pintype "passive"))
      (node (ref "U26") (pin "30") (pinfunction "WAKEUPn_30") (pintype "passive"))
    )
    (net (code "33") (name "VDD3V3_USB") (class "Default")
      (node (ref "C61") (pin "2") (pinfunction "2_2") (pintype "passive"))
      (node (ref "U26") (pin "13") (pinfunction "LDO4OUT_13") (pintype "passive"))
    )
    (net (code "34") (name "VDDA1V8_AON") (class "Default")
      (node (ref "C189") (pin "2") (pinfunction "2_2") (pintype "passive"))
      (node (ref "U26") (pin "14") (pinfunction "LDO1OUT_14") (pintype "passive"))
    )
    (net (code "35") (name "VDDCORE") (class "Default")
      (node (ref "C183") (pin "2") (pinfunction "2_2") (pintype "passive"))
      (node (ref "C22") (pin "2") (pinfunction "2_2") (pintype "passive"))
      (node (ref "C23") (pin "2") (pinfunction "2_2") (pintype "passive"))
      (node (ref "C24") (pin "2") (pinfunction "2_2") (pintype "passive"))
      (node (ref "L2") (pin "2") (pinfunction "2_2") (pintype "passive"))
      (node (ref "LNK2") (pin "2") (pinfunction "2_2") (pintype "passive"))
    )
    (net (code "36") (name "VDDCORE_FB") (class "Default")
      (node (ref "LNK2") (pin "1") (pinfunction "1_1") (pintype "passive"))
      (node (ref "U26") (pin "28") (pinfunction "VOUT2_28") (pintype "passive"))
    )
    (net (code "37") (name "VDDCPU") (class "Default")
      (node (ref "C26") (pin "2") (pinfunction "2_2") (pintype "passive"))
      (node (ref "C27") (pin "2") (pinfunction "2_2") (pintype "passive"))
      (node (ref "C28") (pin "2") (pinfunction "2_2") (pintype "passive"))
      (node (ref "L3") (pin "2") (pinfunction "2_2") (pintype "passive"))
      (node (ref "LNK4") (pin "1") (pinfunction "1_1") (pintype "passive"))
    )
    (net (code "38") (name "VDDCPU_FB") (class "Default")
      (node (ref "LNK4") (pin "2") (pinfunction "2_2") (pintype "passive"))
      (node (ref "U26") (pin "42") (pinfunction "VOUT1_42") (pintype "passive"))
    )
    (net (code "39") (name "VDDGPU") (class "Default")
      (node (ref "C34") (pin "2") (pinfunction "2_2") (pintype "passive"))
      (node (ref "C35") (pin "2") (pinfunction "2_2") (pintype "passive"))
      (node (ref "C36") (pin "2") (pinfunction "2_2") (pintype "passive"))
      (node (ref "C37") (pin "2") (pinfunction "2_2") (pintype "passive"))
      (node (ref "L4") (pin "2") (pinfunction "2_2") (pintype "passive"))
      (node (ref "LNK7") (pin "2") (pinfunction "2_2") (pintype "passive"))
    )
    (net (code "40") (name "VDDGPU_FB") (class "Default")
      (node (ref "LNK7") (pin "1") (pinfunction "1_1") (pintype "passive"))
      (node (ref "U26") (pin "21") (pinfunction "VOUT3_21") (pintype "passive"))
    )
    (net (code "41") (name "VDDIO") (class "Default")
      (node (ref "C185") (pin "2") (pinfunction "2_2") (pintype "passive"))
      (node (ref "C186") (pin "2") (pinfunction "2_2") (pintype "passive"))
      (node (ref "C187") (pin "2") (pinfunction "2_2") (pintype "passive"))
      (node (ref "L6") (pin "2") (pinfunction "2_2") (pintype "passive"))
      (node (ref "LNK11") (pin "2") (pinfunction "2_2") (pintype "passive"))
      (node (ref "U26") (pin "29") (pinfunction "VIO_29") (pintype "passive"))
    )
    (net (code "42") (name "VDDIO_FB") (class "Default")
      (node (ref "LNK11") (pin "1") (pinfunction "1_1") (pintype "passive"))
      (node (ref "U26") (pin "17") (pinfunction "VOUT4_17") (pintype "passive"))
    )
    (net (code "43") (name "VDDIO_SDCARD") (class "Default")
      (node (ref "C217") (pin "1") (pinfunction "1_1") (pintype "passive"))
      (node (ref "U26") (pin "2") (pinfunction "LDO8OUT_2") (pintype "passive"))
    )
    (net (code "44") (name "VDD_DDR") (class "Default")
      (node (ref "C200") (pin "2") (pinfunction "2_2") (pintype "passive"))
      (node (ref "C202") (pin "2") (pinfunction "2_2") (pintype "passive"))
      (node (ref "C39") (pin "2") (pinfunction "2_2") (pintype "passive"))
      (node (ref "C41") (pin "2") (pinfunction "2_2") (pintype "passive"))
      (node (ref "L5") (pin "2") (pinfunction "2_2") (pintype "passive"))
      (node (ref "LNK8") (pin "2") (pinfunction "2_2") (pintype "passive"))
      (node (ref "U26") (pin "43") (pinfunction "LDO3IN_43") (pintype "passive"))
    )
    (net (code "45") (name "VDD_DDR_FB") (class "Default")
      (node (ref "LNK8") (pin "1") (pinfunction "1_1") (pintype "passive"))
      (node (ref "U26") (pin "46") (pinfunction "VOUT6_46") (pintype "passive"))
    )
    (net (code "46") (name "VDD_EMMC") (class "Default")
      (node (ref "C190") (pin "1") (pinfunction "1_1") (pintype "passive"))
      (node (ref "U26") (pin "16") (pinfunction "LDO2OUT_16") (pintype "passive"))
    )
    (net (code "47") (name "VDD_SDCARD") (class "Default")
      (node (ref "C215") (pin "1") (pinfunction "1_1") (pintype "passive"))
      (node (ref "U26") (pin "4") (pinfunction "LDO7OUT_4") (pintype "passive"))
    )
    (net (code "48") (name "VTT_DDR") (class "Default")
      (node (ref "C40") (pin "2") (pinfunction "2_2") (pintype "passive"))
      (node (ref "U26") (pin "44") (pinfunction "LDO3OUT_44") (pintype "passive"))
    )
  )
)
